# door_light.net
KiCad netlist of a schematic drawn in EAGLE
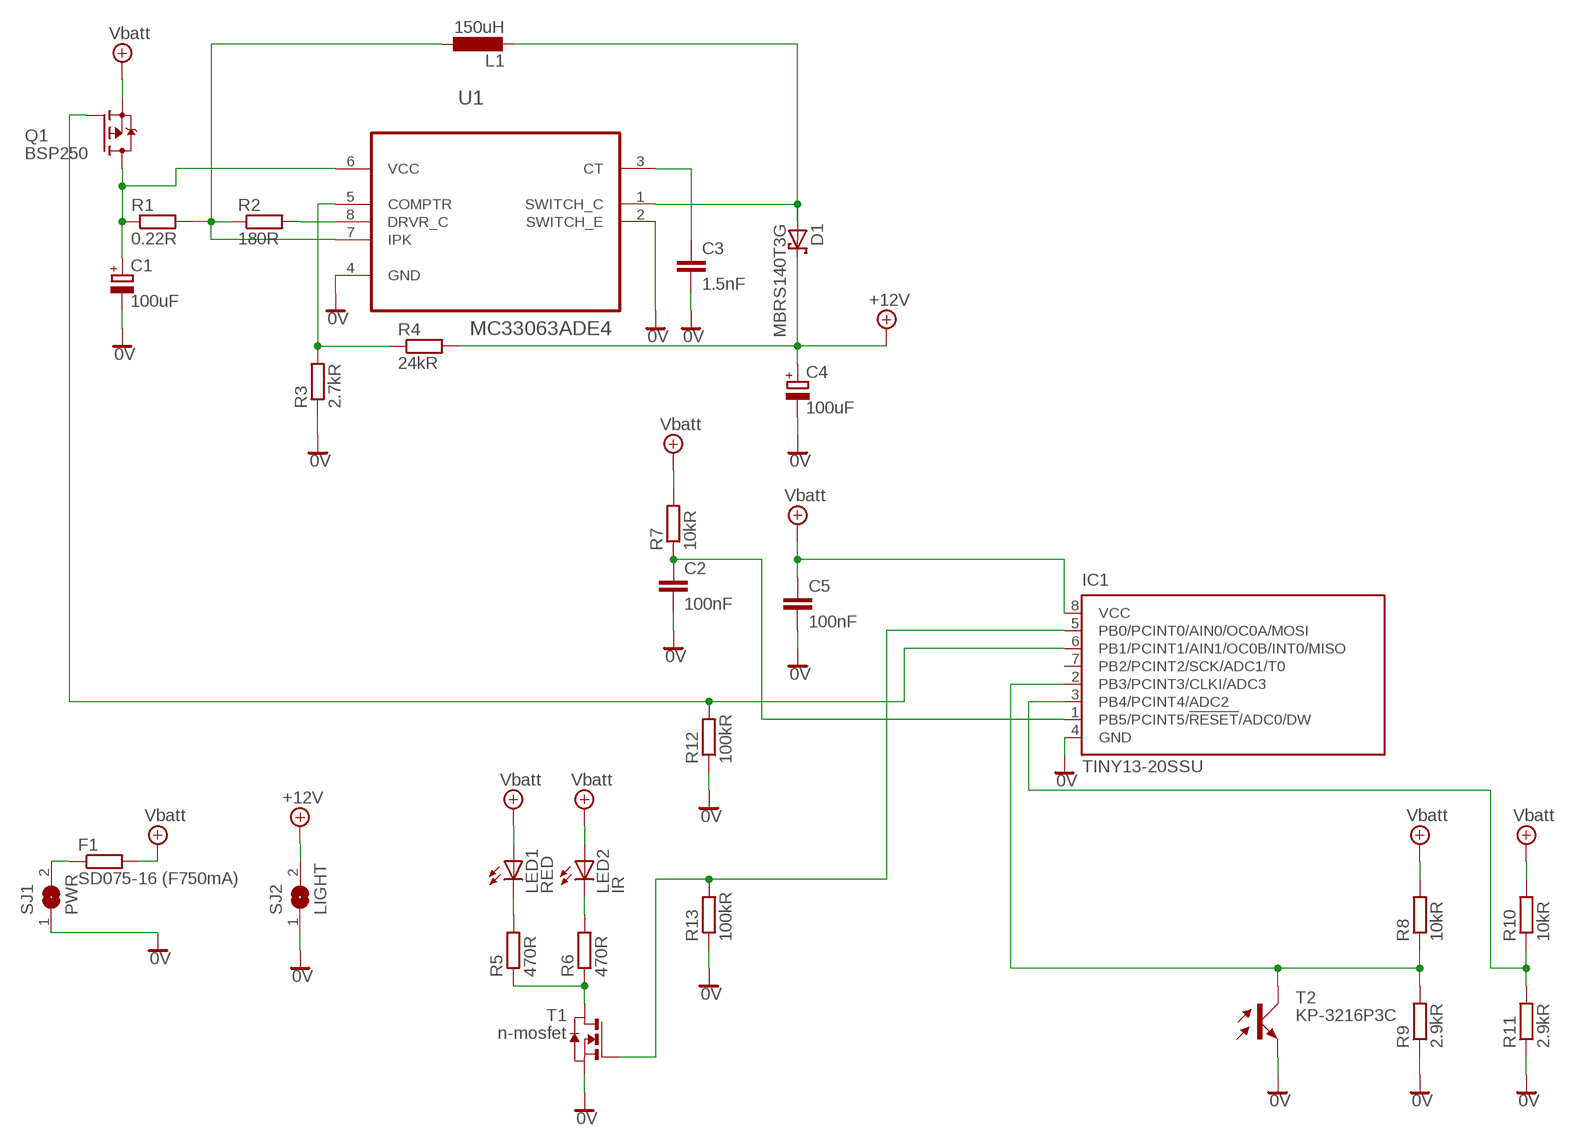
[diagram p0: schematic, sheet 1]

(export (version "E")
  (design (tool "Eeschema 10.0.6"))
  (components
    (comp (ref "C1")
      (value "100uF")
      (footprint "eagle-import:153CLV-0810")
      (libsource (lib "eagle-import") (part "CPOL-EU153CLV-0810"))
    )
    (comp (ref "C2")
      (value "100nF")
      (footprint "eagle-import:C1206")
      (libsource (lib "eagle-import") (part "C-EUC1206"))
    )
    (comp (ref "C3")
      (value "1.5nF")
      (footprint "eagle-import:C1206")
      (libsource (lib "eagle-import") (part "C-EUC1206"))
    )
    (comp (ref "C4")
      (value "100uF")
      (footprint "eagle-import:153CLV-0810")
      (libsource (lib "eagle-import") (part "CPOL-EU153CLV-0810"))
    )
    (comp (ref "C5")
      (value "100nF")
      (footprint "eagle-import:C1206")
      (libsource (lib "eagle-import") (part "C-EUC1206"))
    )
    (comp (ref "D1")
      (value "MBRS140T3G")
      (footprint "eagle-import:SMB")
      (libsource (lib "eagle-import") (part "MBRS130LT3"))
    )
    (comp (ref "F1")
      (value "SD075-16 (F750mA)")
      (footprint "eagle-import:MINI_MELF-0204W")
      (libsource (lib "eagle-import") (part "R-EU_MELF0204W"))
    )
    (comp (ref "IC1")
      (value "TINY13-20SSU")
      (footprint "eagle-import:8S1")
      (fields (field (name "MPN") "ATTINY13-20SSU"))
      (libsource (lib "eagle-import") (part "TINY13SSU-20"))
    )
    (comp (ref "L1")
      (value "150uH")
      (footprint "eagle-import:PIS2816")
      (libsource (lib "eagle-import") (part "L-EUPIS2816"))
    )
    (comp (ref "LED1")
      (value "RED")
      (footprint "eagle-import:CHIPLED_0603")
      (libsource (lib "eagle-import") (part "LEDCHIPLED_0603"))
    )
    (comp (ref "LED2")
      (value "IR")
      (footprint "eagle-import:CHIPLED_1206")
      (libsource (lib "eagle-import") (part "LEDCHIPLED_1206"))
    )
    (comp (ref "Q1")
      (value "BSP250")
      (footprint "eagle-import:SOT223")
      (libsource (lib "eagle-import") (part "BSP170P"))
    )
    (comp (ref "R1")
      (value "0.22R")
      (footprint "eagle-import:M1206")
      (libsource (lib "eagle-import") (part "R-EU_M1206"))
    )
    (comp (ref "R2")
      (value "180R")
      (footprint "eagle-import:R0603")
      (libsource (lib "eagle-import") (part "R-EU_R0603"))
    )
    (comp (ref "R3")
      (value "2.7kR")
      (footprint "eagle-import:R0603")
      (libsource (lib "eagle-import") (part "R-EU_R0603"))
    )
    (comp (ref "R4")
      (value "24kR")
      (footprint "eagle-import:R0603")
      (libsource (lib "eagle-import") (part "R-EU_R0603"))
    )
    (comp (ref "R5")
      (value "470R")
      (footprint "eagle-import:R0603")
      (libsource (lib "eagle-import") (part "R-EU_R0603"))
    )
    (comp (ref "R6")
      (value "470R")
      (footprint "eagle-import:R0603")
      (libsource (lib "eagle-import") (part "R-EU_R0603"))
    )
    (comp (ref "R7")
      (value "10kR")
      (footprint "eagle-import:R0402")
      (libsource (lib "eagle-import") (part "R-EU_R0402"))
    )
    (comp (ref "R8")
      (value "10kR")
      (footprint "eagle-import:R0603")
      (libsource (lib "eagle-import") (part "R-EU_R0603"))
    )
    (comp (ref "R9")
      (value "2.9kR")
      (footprint "eagle-import:R0603")
      (libsource (lib "eagle-import") (part "R-EU_R0603"))
    )
    (comp (ref "R10")
      (value "10kR")
      (footprint "eagle-import:R0603")
      (libsource (lib "eagle-import") (part "R-EU_R0603"))
    )
    (comp (ref "R11")
      (value "2.9kR")
      (footprint "eagle-import:R0603")
      (libsource (lib "eagle-import") (part "R-EU_R0603"))
    )
    (comp (ref "R12")
      (value "100kR")
      (footprint "eagle-import:R0603")
      (libsource (lib "eagle-import") (part "R-EU_R0603"))
    )
    (comp (ref "R13")
      (value "100kR")
      (footprint "eagle-import:R0603")
      (libsource (lib "eagle-import") (part "R-EU_R0603"))
    )
    (comp (ref "SJ1")
      (value "PWR")
      (footprint "eagle-import:SJW")
      (libsource (lib "eagle-import") (part "SJW"))
    )
    (comp (ref "SJ2")
      (value "LIGHT")
      (footprint "eagle-import:SJW")
      (libsource (lib "eagle-import") (part "SJW"))
    )
    (comp (ref "T1")
      (value "n-mosfet")
      (footprint "eagle-import:SOT-23")
      (libsource (lib "eagle-import") (part "NMOSSOT23"))
    )
    (comp (ref "T2")
      (value "KP-3216P3C")
      (footprint "eagle-import:OPTO-TRANS-SIEMENS_BP103")
      (libsource (lib "eagle-import") (part "KP-3216P3C"))
    )
    (comp (ref "U1")
      (value "MC33063ADE4")
      (footprint "eagle-import:SOIC127P600X175-8N")
      (libsource (lib "eagle-import") (part "MC33063ADE4"))
    )
  )
  (nets
    (net (code "1") (name "+12V") (class "Default")
      (node (ref "C4") (pin "+") (pinfunction "+_+") (pintype "passive"))
      (node (ref "D1") (pin "C") (pinfunction "C_C") (pintype "passive"))
      (node (ref "R4") (pin "2") (pinfunction "2_2") (pintype "passive"))
      (node (ref "SJ2") (pin "2") (pinfunction "2_2") (pintype "passive"))
    )
    (net (code "2") (name "0V") (class "Default")
      (node (ref "C1") (pin "-") (pinfunction "-_-") (pintype "passive"))
      (node (ref "C2") (pin "2") (pinfunction "2_2") (pintype "passive"))
      (node (ref "C3") (pin "2") (pinfunction "2_2") (pintype "passive"))
      (node (ref "C4") (pin "-") (pinfunction "-_-") (pintype "passive"))
      (node (ref "C5") (pin "2") (pinfunction "2_2") (pintype "passive"))
      (node (ref "IC1") (pin "4") (pinfunction "GND_4") (pintype "power_in"))
      (node (ref "R11") (pin "1") (pinfunction "1_1") (pintype "passive"))
      (node (ref "R12") (pin "1") (pinfunction "1_1") (pintype "passive"))
      (node (ref "R13") (pin "1") (pinfunction "1_1") (pintype "passive"))
      (node (ref "R3") (pin "1") (pinfunction "1_1") (pintype "passive"))
      (node (ref "R9") (pin "1") (pinfunction "1_1") (pintype "passive"))
      (node (ref "SJ1") (pin "1") (pinfunction "1_1") (pintype "passive"))
      (node (ref "SJ2") (pin "1") (pinfunction "1_1") (pintype "passive"))
      (node (ref "T1") (pin "2") (pinfunction "S_2") (pintype "passive"))
      (node (ref "T2") (pin "EMITER") (pinfunction "E_EMITER") (pintype "passive"))
      (node (ref "U1") (pin "2") (pinfunction "SWITCH_E_2") (pintype "passive"))
      (node (ref "U1") (pin "4") (pinfunction "GND_4") (pintype "passive"))
    )
    (net (code "3") (name "Net-(F1-Pad1)") (class "Default")
      (node (ref "F1") (pin "1") (pinfunction "1_1") (pintype "passive"))
      (node (ref "SJ1") (pin "2") (pinfunction "2_2") (pintype "passive"))
    )
    (net (code "4") (name "Net-(IC1-PB0{slash}PCINT0{slash}AIN0{slash}OC0A{slash}MOSI)") (class "Default")
      (node (ref "IC1") (pin "5") (pinfunction "PB0/PCINT0/AIN0/OC0A/MOSI_5") (pintype "bidirectional"))
      (node (ref "R13") (pin "2") (pinfunction "2_2") (pintype "passive"))
      (node (ref "T1") (pin "3") (pinfunction "G_3") (pintype "passive"))
    )
    (net (code "5") (name "Net-(IC1-PB1{slash}PCINT1{slash}AIN1{slash}OC0B{slash}INT0{slash}MISO)") (class "Default")
      (node (ref "IC1") (pin "6") (pinfunction "PB1/PCINT1/AIN1/OC0B/INT0/MISO_6") (pintype "bidirectional"))
      (node (ref "Q1") (pin "1") (pinfunction "G_1") (pintype "passive"))
      (node (ref "R12") (pin "2") (pinfunction "2_2") (pintype "passive"))
    )
    (net (code "6") (name "Net-(IC1-PB3{slash}PCINT3{slash}CLKI{slash}ADC3)") (class "Default")
      (node (ref "IC1") (pin "2") (pinfunction "PB3/PCINT3/CLKI/ADC3_2") (pintype "bidirectional"))
      (node (ref "R8") (pin "1") (pinfunction "1_1") (pintype "passive"))
      (node (ref "R9") (pin "2") (pinfunction "2_2") (pintype "passive"))
      (node (ref "T2") (pin "COLLECTOR") (pinfunction "C_COLLECTOR") (pintype "passive"))
    )
    (net (code "7") (name "Net-(IC1-PB4{slash}PCINT4{slash}ADC2)") (class "Default")
      (node (ref "IC1") (pin "3") (pinfunction "PB4/PCINT4/ADC2_3") (pintype "bidirectional"))
      (node (ref "R10") (pin "1") (pinfunction "1_1") (pintype "passive"))
      (node (ref "R11") (pin "2") (pinfunction "2_2") (pintype "passive"))
    )
    (net (code "8") (name "Net-(IC1-PB5{slash}PCINT5{slash}~{RESET}{slash}ADC0{slash}DW)") (class "Default")
      (node (ref "C2") (pin "1") (pinfunction "1_1") (pintype "passive"))
      (node (ref "IC1") (pin "1") (pinfunction "PB5/PCINT5/~{RESET}/ADC0/DW_1") (pintype "bidirectional"))
      (node (ref "R7") (pin "1") (pinfunction "1_1") (pintype "passive"))
    )
    (net (code "9") (name "Net-(LED1-PadC)") (class "Default")
      (node (ref "LED1") (pin "C") (pinfunction "C_C") (pintype "passive"))
      (node (ref "R5") (pin "2") (pinfunction "2_2") (pintype "passive"))
    )
    (net (code "10") (name "Net-(LED2-PadC)") (class "Default")
      (node (ref "LED2") (pin "C") (pinfunction "C_C") (pintype "passive"))
      (node (ref "R6") (pin "2") (pinfunction "2_2") (pintype "passive"))
    )
    (net (code "11") (name "Net-(T1-D)") (class "Default")
      (node (ref "R5") (pin "1") (pinfunction "1_1") (pintype "passive"))
      (node (ref "R6") (pin "1") (pinfunction "1_1") (pintype "passive"))
      (node (ref "T1") (pin "1") (pinfunction "D_1") (pintype "passive"))
    )
    (net (code "12") (name "Net-(U1-COMPTR)") (class "Default")
      (node (ref "R3") (pin "2") (pinfunction "2_2") (pintype "passive"))
      (node (ref "R4") (pin "1") (pinfunction "1_1") (pintype "passive"))
      (node (ref "U1") (pin "5") (pinfunction "COMPTR_5") (pintype "passive"))
    )
    (net (code "13") (name "Net-(U1-CT)") (class "Default")
      (node (ref "C3") (pin "1") (pinfunction "1_1") (pintype "passive"))
      (node (ref "U1") (pin "3") (pinfunction "CT_3") (pintype "passive"))
    )
    (net (code "14") (name "Net-(U1-DRVR_C)") (class "Default")
      (node (ref "R2") (pin "2") (pinfunction "2_2") (pintype "passive"))
      (node (ref "U1") (pin "8") (pinfunction "DRVR_C_8") (pintype "passive"))
    )
    (net (code "15") (name "Net-(U1-IPK)") (class "Default")
      (node (ref "L1") (pin "1") (pinfunction "1_1") (pintype "passive"))
      (node (ref "R1") (pin "2") (pinfunction "2_2") (pintype "passive"))
      (node (ref "R2") (pin "1") (pinfunction "1_1") (pintype "passive"))
      (node (ref "U1") (pin "7") (pinfunction "IPK_7") (pintype "passive"))
    )
    (net (code "16") (name "Net-(U1-SWITCH_C)") (class "Default")
      (node (ref "D1") (pin "A") (pinfunction "A_A") (pintype "passive"))
      (node (ref "L1") (pin "2") (pinfunction "2_2") (pintype "passive"))
      (node (ref "U1") (pin "1") (pinfunction "SWITCH_C_1") (pintype "passive"))
    )
    (net (code "17") (name "Net-(U1-VCC)") (class "Default")
      (node (ref "C1") (pin "+") (pinfunction "+_+") (pintype "passive"))
      (node (ref "Q1") (pin "2") (pinfunction "D_2") (pintype "passive"))
      (node (ref "Q1") (pin "4") (pinfunction "D_4") (pintype "passive"))
      (node (ref "R1") (pin "1") (pinfunction "1_1") (pintype "passive"))
      (node (ref "U1") (pin "6") (pinfunction "VCC_6") (pintype "power_in"))
    )
    (net (code "18") (name "Vbatt") (class "Default")
      (node (ref "C5") (pin "1") (pinfunction "1_1") (pintype "passive"))
      (node (ref "F1") (pin "2") (pinfunction "2_2") (pintype "passive"))
      (node (ref "IC1") (pin "8") (pinfunction "VCC_8") (pintype "power_in"))
      (node (ref "LED1") (pin "A") (pinfunction "A_A") (pintype "passive"))
      (node (ref "LED2") (pin "A") (pinfunction "A_A") (pintype "passive"))
      (node (ref "Q1") (pin "3") (pinfunction "S_3") (pintype "passive"))
      (node (ref "R10") (pin "2") (pinfunction "2_2") (pintype "passive"))
      (node (ref "R7") (pin "2") (pinfunction "2_2") (pintype "passive"))
      (node (ref "R8") (pin "2") (pinfunction "2_2") (pintype "passive"))
    )
    (net (code "19") (name "unconnected-(IC1-PB2{slash}PCINT2{slash}SCK{slash}ADC1{slash}T0-Pad7)") (class "Default")
      (node (ref "IC1") (pin "7") (pinfunction "PB2/PCINT2/SCK/ADC1/T0_7") (pintype "bidirectional"))
    )
  )
)
